# PWMController.net
KiCad netlist of a schematic drawn in EAGLE
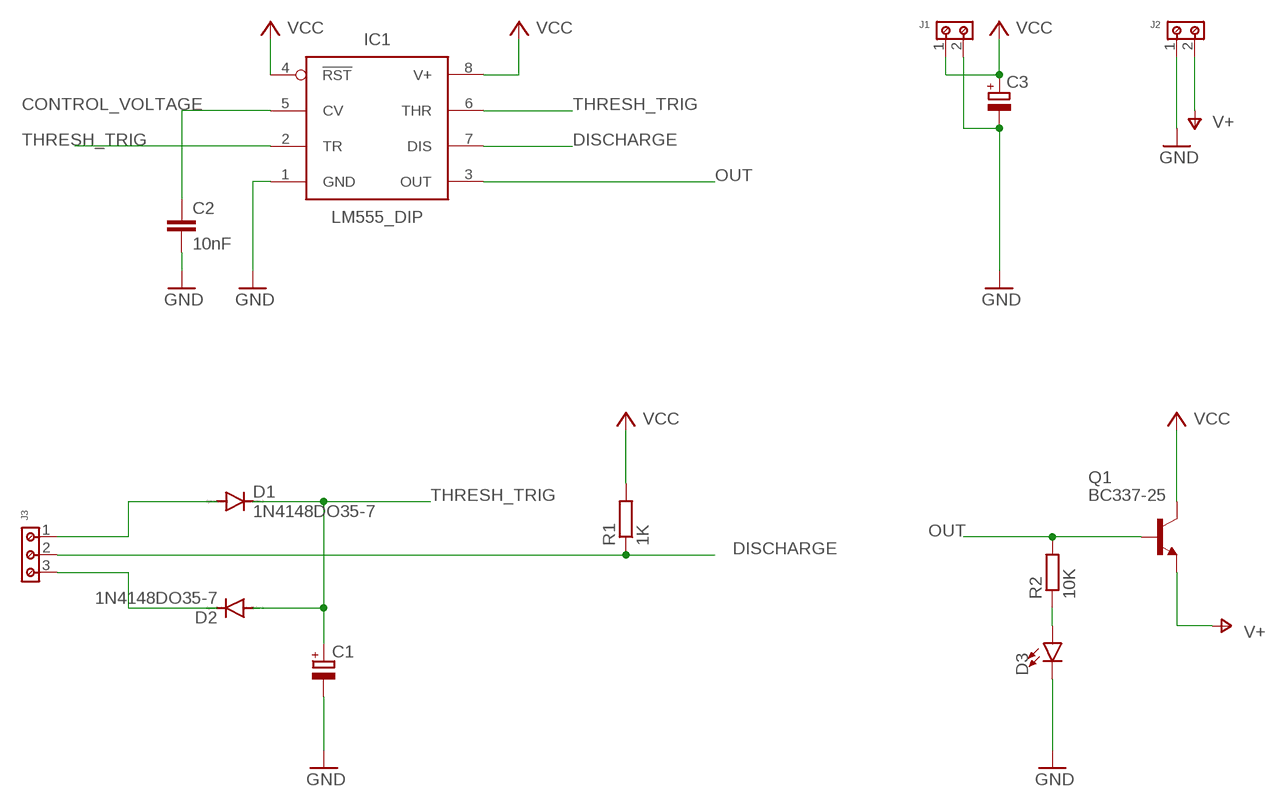
[diagram p0: schematic, sheet 1]

(export (version "E")
  (design (tool "Eeschema 10.0.6"))
  (components
    (comp (ref "C1")
      (value "2.2uF")
      (footprint "eagle-import:E1,8-4")
      (libsource (lib "eagle-import") (part "CPOL-EUE1.8-4"))
    )
    (comp (ref "C2")
      (value "10nF")
      (footprint "eagle-import:CAPC3216X135")
      (libsource (lib "eagle-import") (part "CCHIP-1206(3216-METRIC)_"))
    )
    (comp (ref "C3")
      (value "100mF")
      (footprint "eagle-import:E1,8-4")
      (libsource (lib "eagle-import") (part "CPOL-EUE1.8-4"))
    )
    (comp (ref "D1")
      (value "1N4148DO35-7")
      (footprint "eagle-import:DO35-7")
      (libsource (lib "eagle-import") (part "1N4148DO35-7"))
    )
    (comp (ref "D2")
      (value "1N4148DO35-7")
      (footprint "eagle-import:DO35-7")
      (libsource (lib "eagle-import") (part "1N4148DO35-7"))
    )
    (comp (ref "D3")
      (value "LED5MM")
      (footprint "eagle-import:LED5MM")
      (libsource (lib "eagle-import") (part "LED5MM"))
    )
    (comp (ref "IC1")
      (value "LM555_DIP")
      (footprint "eagle-import:DIP826W53P254L959H508Q8B")
      (fields (field (name "MANUFACTURER") "Texas Instruments ") (field (name "MPN") "LM555CN/NOPB "))
      (libsource (lib "eagle-import") (part "555_DIPLM"))
    )
    (comp (ref "J1")
      (value "691213510002")
      (footprint "eagle-import:691213510002")
      (libsource (lib "eagle-import") (part "691213510002"))
    )
    (comp (ref "J2")
      (value "691213510002")
      (footprint "eagle-import:691213510002")
      (libsource (lib "eagle-import") (part "691213510002"))
    )
    (comp (ref "J3")
      (value "691213510003")
      (footprint "eagle-import:691213510003")
      (libsource (lib "eagle-import") (part "691213510003"))
    )
    (comp (ref "Q1")
      (value "BC337-25")
      (footprint "eagle-import:TO92")
      (libsource (lib "eagle-import") (part "BC337-25"))
    )
    (comp (ref "R1")
      (value "1K")
      (footprint "eagle-import:R1206")
      (libsource (lib "eagle-import") (part "R-EU_R1206"))
    )
    (comp (ref "R2")
      (value "10K")
      (footprint "eagle-import:R1206")
      (libsource (lib "eagle-import") (part "R-EU_R1206"))
    )
  )
  (nets
    (net (code "1") (name "/CONTROL_VOLTAGE") (class "Default")
      (node (ref "C2") (pin "1") (pinfunction "1_1") (pintype "passive"))
      (node (ref "IC1") (pin "5") (pinfunction "CV_5") (pintype "input"))
    )
    (net (code "2") (name "/DISCHARGE") (class "Default")
      (node (ref "IC1") (pin "7") (pinfunction "DIS_7") (pintype "input"))
      (node (ref "J3") (pin "2") (pinfunction "2_2") (pintype "passive"))
      (node (ref "R1") (pin "1") (pinfunction "1_1") (pintype "passive"))
    )
    (net (code "3") (name "/OUT") (class "Default")
      (node (ref "IC1") (pin "3") (pinfunction "OUT_3") (pintype "output"))
      (node (ref "Q1") (pin "2") (pinfunction "B_2") (pintype "passive"))
      (node (ref "R2") (pin "2") (pinfunction "2_2") (pintype "passive"))
    )
    (net (code "4") (name "/THRESH_TRIG") (class "Default")
      (node (ref "C1") (pin "+") (pinfunction "+_+") (pintype "passive"))
      (node (ref "D1") (pin "C") (pinfunction "C_C") (pintype "passive"))
      (node (ref "D2") (pin "A") (pinfunction "A_A") (pintype "passive"))
      (node (ref "IC1") (pin "2") (pinfunction "TR_2") (pintype "input"))
      (node (ref "IC1") (pin "6") (pinfunction "THR_6") (pintype "input"))
    )
    (net (code "5") (name "GND") (class "Default")
      (node (ref "C1") (pin "-") (pinfunction "-_-") (pintype "passive"))
      (node (ref "C2") (pin "2") (pinfunction "2_2") (pintype "passive"))
      (node (ref "C3") (pin "-") (pinfunction "-_-") (pintype "passive"))
      (node (ref "D3") (pin "K") (pinfunction "C_K") (pintype "passive"))
      (node (ref "IC1") (pin "1") (pinfunction "GND_1") (pintype "power_in"))
      (node (ref "J1") (pin "2") (pinfunction "2_2") (pintype "passive"))
      (node (ref "J2") (pin "1") (pinfunction "1_1") (pintype "passive"))
    )
    (net (code "6") (name "Net-(D1-PadA)") (class "Default")
      (node (ref "D1") (pin "A") (pinfunction "A_A") (pintype "passive"))
      (node (ref "J3") (pin "1") (pinfunction "1_1") (pintype "passive"))
    )
    (net (code "7") (name "Net-(D2-PadC)") (class "Default")
      (node (ref "D2") (pin "C") (pinfunction "C_C") (pintype "passive"))
      (node (ref "J3") (pin "3") (pinfunction "3_3") (pintype "passive"))
    )
    (net (code "8") (name "Net-(D3-PadA)") (class "Default")
      (node (ref "D3") (pin "A") (pinfunction "A_A") (pintype "passive"))
      (node (ref "R2") (pin "1") (pinfunction "1_1") (pintype "passive"))
    )
    (net (code "9") (name "V+") (class "Default")
      (node (ref "J2") (pin "2") (pinfunction "2_2") (pintype "passive"))
      (node (ref "Q1") (pin "1") (pinfunction "E_1") (pintype "passive"))
    )
    (net (code "10") (name "VCC") (class "Default")
      (node (ref "C3") (pin "+") (pinfunction "+_+") (pintype "passive"))
      (node (ref "IC1") (pin "4") (pinfunction "~{RST}_4") (pintype "input"))
      (node (ref "IC1") (pin "8") (pinfunction "V+_8") (pintype "power_in"))
      (node (ref "J1") (pin "1") (pinfunction "1_1") (pintype "passive"))
      (node (ref "Q1") (pin "3") (pinfunction "C_3") (pintype "passive"))
      (node (ref "R1") (pin "2") (pinfunction "2_2") (pintype "passive"))
    )
  )
)
